# schematic.net
KiCad netlist of a schematic drawn in EAGLE
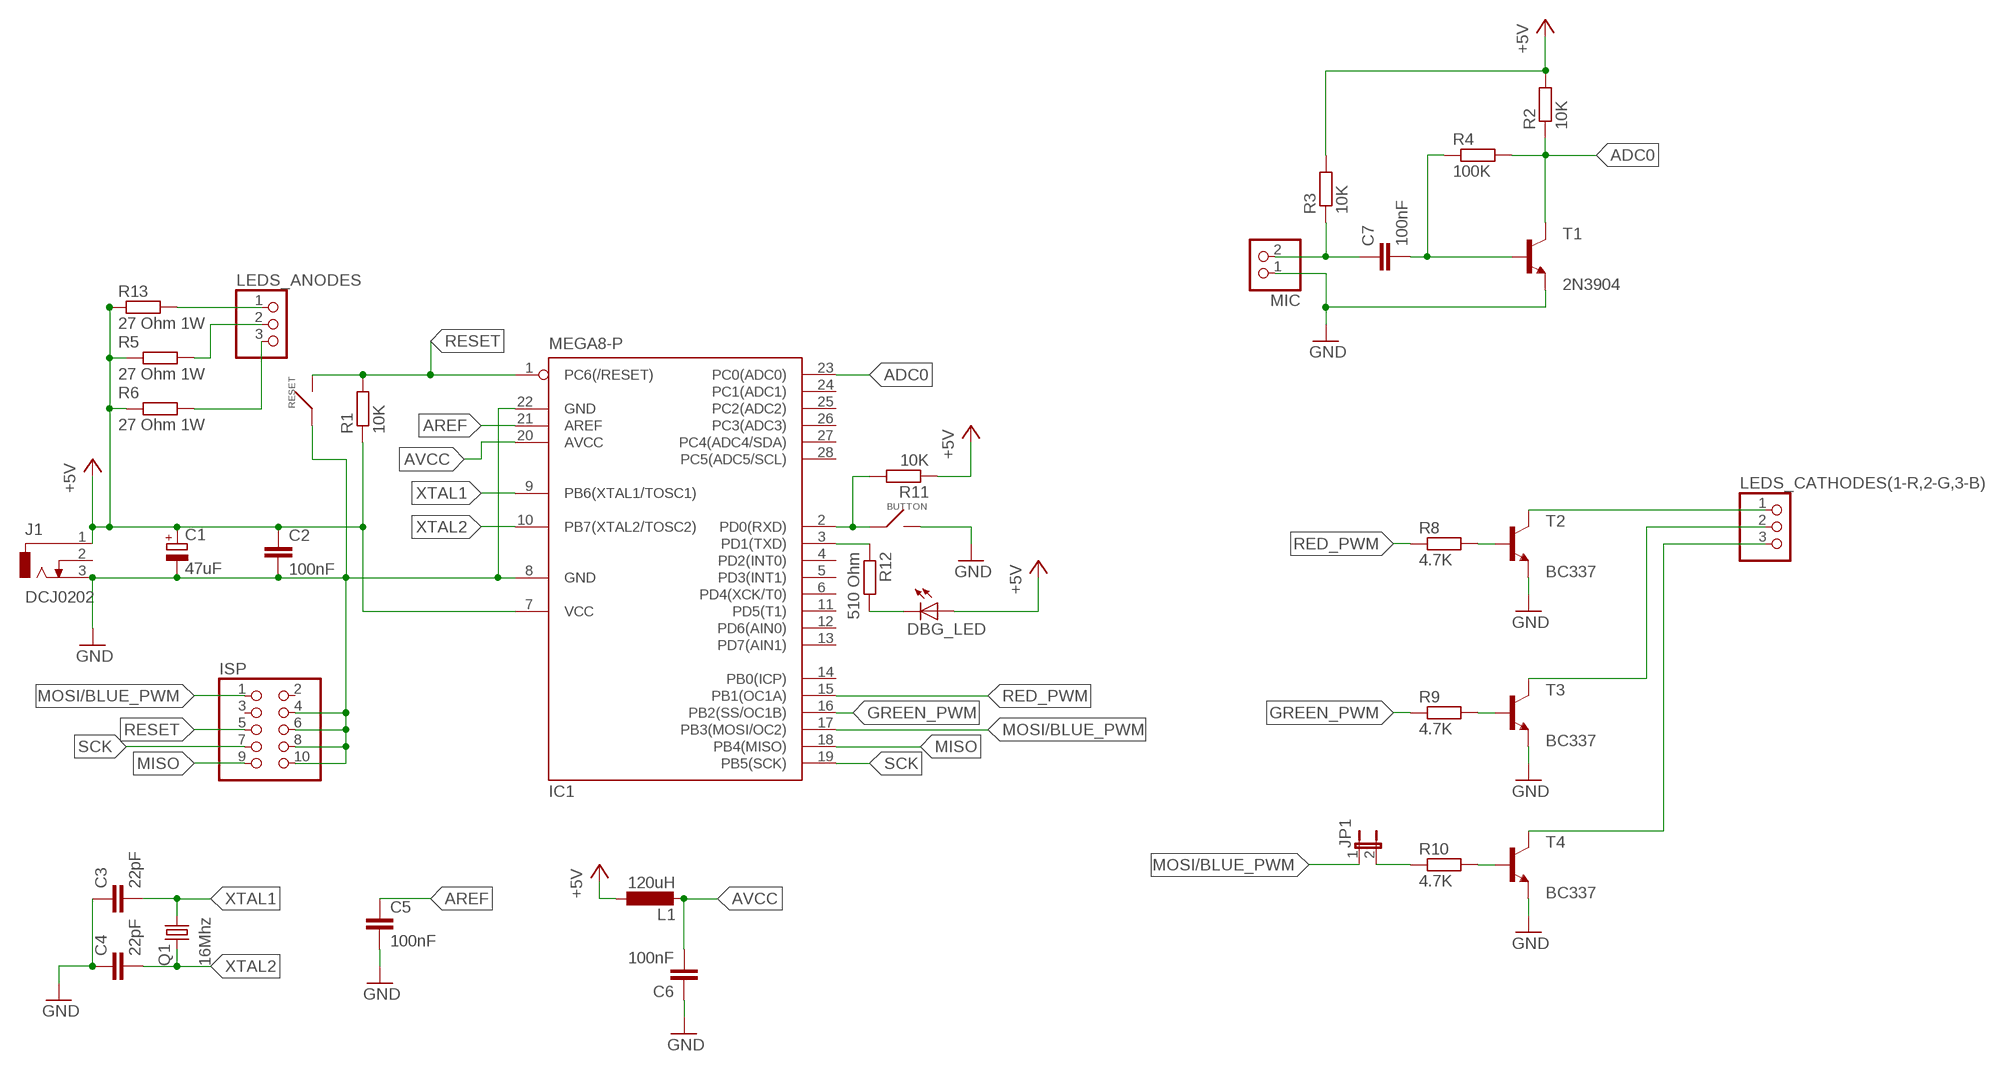
[diagram p0: schematic, sheet 1]

(export (version "E")
  (design (tool "Eeschema 10.0.6"))
  (components
    (comp (ref "BUTTON")
      (value "TS1102")
      (footprint "eagle-import:TL1105")
      (libsource (lib "eagle-import") (part "TS1102"))
    )
    (comp (ref "C1")
      (value "47uF")
      (footprint "eagle-import:E2-4")
      (libsource (lib "eagle-import") (part "CPOL-EUE2-4"))
    )
    (comp (ref "C2")
      (value "100nF")
      (footprint "eagle-import:C1206")
      (libsource (lib "eagle-import") (part "C-EUC1206"))
    )
    (comp (ref "C3")
      (value "22pF")
      (footprint "eagle-import:C050-024X044")
      (libsource (lib "eagle-import") (part "C-EU050-024X044"))
    )
    (comp (ref "C4")
      (value "22pF")
      (footprint "eagle-import:C050-024X044")
      (libsource (lib "eagle-import") (part "C-EU050-024X044"))
    )
    (comp (ref "C5")
      (value "100nF")
      (footprint "eagle-import:C1206")
      (libsource (lib "eagle-import") (part "C-EUC1206"))
    )
    (comp (ref "C6")
      (value "100nF")
      (footprint "eagle-import:C1206")
      (libsource (lib "eagle-import") (part "C-EUC1206"))
    )
    (comp (ref "C7")
      (value "100nF")
      (footprint "eagle-import:C1206")
      (libsource (lib "eagle-import") (part "C-EUC1206"))
    )
    (comp (ref "DBG_LED")
      (value "LED3MM")
      (footprint "eagle-import:LED3MM")
      (libsource (lib "eagle-import") (part "LED3MM"))
    )
    (comp (ref "IC1")
      (value "MEGA8-P")
      (footprint "eagle-import:DIL28-3")
      (libsource (lib "eagle-import") (part "MEGA8-P"))
    )
    (comp (ref "ISP")
      (value "PINHD-2X5")
      (footprint "eagle-import:2X05")
      (libsource (lib "eagle-import") (part "PINHD-2X5"))
    )
    (comp (ref "J1")
      (value "DCJ0202")
      (footprint "eagle-import:DCJ0202")
      (libsource (lib "eagle-import") (part "DCJ0202"))
    )
    (comp (ref "JP1")
      (value "JP1E")
      (footprint "eagle-import:JP1")
      (libsource (lib "eagle-import") (part "JP1E"))
    )
    (comp (ref "L1")
      (value "120uH")
      (footprint "eagle-import:2200-15.24")
      (libsource (lib "eagle-import") (part "L-EU2200-15.24"))
    )
    (comp (ref "LEDS_ANODES")
      (value "PINHD-1X3")
      (footprint "eagle-import:1X03")
      (libsource (lib "eagle-import") (part "PINHD-1X3"))
    )
    (comp (ref "LEDS_CATHODES(1-R,2-G,3-B)")
      (value "PINHD-1X3")
      (footprint "eagle-import:1X03")
      (libsource (lib "eagle-import") (part "PINHD-1X3"))
    )
    (comp (ref "MIC")
      (value "PINHD-1X2")
      (footprint "eagle-import:1X02")
      (libsource (lib "eagle-import") (part "PINHD-1X2"))
    )
    (comp (ref "Q1")
      (value "16Mhz")
      (footprint "eagle-import:HC49_S")
      (libsource (lib "eagle-import") (part "CRYSTALHC49S"))
    )
    (comp (ref "R1")
      (value "10K")
      (footprint "eagle-import:M1206")
      (libsource (lib "eagle-import") (part "R-EU_M1206"))
    )
    (comp (ref "R2")
      (value "10K")
      (footprint "eagle-import:M1206")
      (libsource (lib "eagle-import") (part "R-EU_M1206"))
    )
    (comp (ref "R3")
      (value "10K")
      (footprint "eagle-import:M1206")
      (libsource (lib "eagle-import") (part "R-EU_M1206"))
    )
    (comp (ref "R4")
      (value "100K")
      (footprint "eagle-import:M0805")
      (libsource (lib "eagle-import") (part "R-EU_M0805"))
    )
    (comp (ref "R5")
      (value "27 Ohm 1W")
      (footprint "eagle-import:0207_12")
      (libsource (lib "eagle-import") (part "R-EU_0207/12"))
    )
    (comp (ref "R6")
      (value "27 Ohm 1W")
      (footprint "eagle-import:0207_12")
      (libsource (lib "eagle-import") (part "R-EU_0207/12"))
    )
    (comp (ref "R8")
      (value "4.7K")
      (footprint "eagle-import:M0805")
      (libsource (lib "eagle-import") (part "R-EU_M0805"))
    )
    (comp (ref "R9")
      (value "4.7K")
      (footprint "eagle-import:M0805")
      (libsource (lib "eagle-import") (part "R-EU_M0805"))
    )
    (comp (ref "R10")
      (value "4.7K")
      (footprint "eagle-import:M0805")
      (libsource (lib "eagle-import") (part "R-EU_M0805"))
    )
    (comp (ref "R11")
      (value "10K")
      (footprint "eagle-import:M1206")
      (libsource (lib "eagle-import") (part "R-EU_M1206"))
    )
    (comp (ref "R12")
      (value "510 Ohm")
      (footprint "eagle-import:M1206")
      (libsource (lib "eagle-import") (part "R-EU_M1206"))
    )
    (comp (ref "R13")
      (value "27 Ohm 1W")
      (footprint "eagle-import:0207_12")
      (libsource (lib "eagle-import") (part "R-EU_0207/12"))
    )
    (comp (ref "RESET")
      (value "TS1102")
      (footprint "eagle-import:TL1105")
      (libsource (lib "eagle-import") (part "TS1102"))
    )
    (comp (ref "T1")
      (value "2N3904")
      (footprint "eagle-import:TO92")
      (libsource (lib "eagle-import") (part "2N3904"))
    )
    (comp (ref "T2")
      (value "BC337")
      (footprint "eagle-import:TO92")
      (libsource (lib "eagle-import") (part "BC337"))
    )
    (comp (ref "T3")
      (value "BC337")
      (footprint "eagle-import:TO92")
      (libsource (lib "eagle-import") (part "BC337"))
    )
    (comp (ref "T4")
      (value "BC337")
      (footprint "eagle-import:TO92")
      (libsource (lib "eagle-import") (part "BC337"))
    )
  )
  (nets
    (net (code "1") (name "+5V") (class "Default")
      (node (ref "C1") (pin "+") (pinfunction "+_+") (pintype "passive"))
      (node (ref "C2") (pin "1") (pinfunction "1_1") (pintype "passive"))
      (node (ref "DBG_LED") (pin "A") (pinfunction "A_A") (pintype "passive"))
      (node (ref "IC1") (pin "7") (pinfunction "VCC_7") (pintype "power_in"))
      (node (ref "J1") (pin "1") (pinfunction "1_1") (pintype "passive"))
      (node (ref "L1") (pin "1") (pinfunction "1_1") (pintype "passive"))
      (node (ref "R1") (pin "1") (pinfunction "1_1") (pintype "passive"))
      (node (ref "R11") (pin "1") (pinfunction "1_1") (pintype "passive"))
      (node (ref "R13") (pin "1") (pinfunction "1_1") (pintype "passive"))
      (node (ref "R2") (pin "2") (pinfunction "2_2") (pintype "passive"))
      (node (ref "R3") (pin "2") (pinfunction "2_2") (pintype "passive"))
      (node (ref "R5") (pin "1") (pinfunction "1_1") (pintype "passive"))
      (node (ref "R6") (pin "1") (pinfunction "1_1") (pintype "passive"))
    )
    (net (code "2") (name "ADC0") (class "Default")
      (node (ref "IC1") (pin "23") (pinfunction "PC0(ADC0)_23") (pintype "bidirectional"))
      (node (ref "R2") (pin "1") (pinfunction "1_1") (pintype "passive"))
      (node (ref "R4") (pin "2") (pinfunction "2_2") (pintype "passive"))
      (node (ref "T1") (pin "1") (pinfunction "C_1") (pintype "passive"))
    )
    (net (code "3") (name "AREF") (class "Default")
      (node (ref "C5") (pin "1") (pinfunction "1_1") (pintype "passive"))
      (node (ref "IC1") (pin "21") (pinfunction "AREF_21") (pintype "passive"))
    )
    (net (code "4") (name "AVCC") (class "Default")
      (node (ref "C6") (pin "2") (pinfunction "2_2") (pintype "passive"))
      (node (ref "IC1") (pin "20") (pinfunction "AVCC_20") (pintype "power_in"))
      (node (ref "L1") (pin "2") (pinfunction "2_2") (pintype "passive"))
    )
    (net (code "5") (name "GND") (class "Default")
      (node (ref "BUTTON") (pin "2") (pinfunction "P$2_2") (pintype "bidirectional"))
      (node (ref "C1") (pin "-") (pinfunction "-_-") (pintype "passive"))
      (node (ref "C2") (pin "2") (pinfunction "2_2") (pintype "passive"))
      (node (ref "C3") (pin "1") (pinfunction "1_1") (pintype "passive"))
      (node (ref "C4") (pin "1") (pinfunction "1_1") (pintype "passive"))
      (node (ref "C5") (pin "2") (pinfunction "2_2") (pintype "passive"))
      (node (ref "C6") (pin "1") (pinfunction "1_1") (pintype "passive"))
      (node (ref "IC1") (pin "22") (pinfunction "GND_22") (pintype "power_in"))
      (node (ref "IC1") (pin "8") (pinfunction "GND_8") (pintype "power_in"))
      (node (ref "ISP") (pin "10") (pinfunction "10_10") (pintype "passive"))
      (node (ref "ISP") (pin "4") (pinfunction "4_4") (pintype "passive"))
      (node (ref "ISP") (pin "6") (pinfunction "6_6") (pintype "passive"))
      (node (ref "ISP") (pin "8") (pinfunction "8_8") (pintype "passive"))
      (node (ref "J1") (pin "3") (pinfunction "3_3") (pintype "passive"))
      (node (ref "MIC") (pin "1") (pinfunction "1_1") (pintype "passive"))
      (node (ref "RESET") (pin "1") (pinfunction "P$1_1") (pintype "bidirectional"))
      (node (ref "T1") (pin "3") (pinfunction "E_3") (pintype "passive"))
      (node (ref "T2") (pin "1") (pinfunction "E_1") (pintype "passive"))
      (node (ref "T3") (pin "1") (pinfunction "E_1") (pintype "passive"))
      (node (ref "T4") (pin "1") (pinfunction "E_1") (pintype "passive"))
    )
    (net (code "6") (name "GREEN_PWM") (class "Default")
      (node (ref "IC1") (pin "16") (pinfunction "PB2(SS/OC1B)_16") (pintype "bidirectional"))
      (node (ref "R9") (pin "1") (pinfunction "1_1") (pintype "passive"))
    )
    (net (code "7") (name "MISO") (class "Default")
      (node (ref "IC1") (pin "18") (pinfunction "PB4(MISO)_18") (pintype "bidirectional"))
      (node (ref "ISP") (pin "9") (pinfunction "9_9") (pintype "passive"))
    )
    (net (code "8") (name "MOSI{slash}BLUE_PWM") (class "Default")
      (node (ref "IC1") (pin "17") (pinfunction "PB3(MOSI/OC2)_17") (pintype "bidirectional"))
      (node (ref "ISP") (pin "1") (pinfunction "1_1") (pintype "passive"))
      (node (ref "JP1") (pin "1") (pinfunction "1_1") (pintype "passive"))
    )
    (net (code "9") (name "Net-(BUTTON-P$1)") (class "Default")
      (node (ref "BUTTON") (pin "1") (pinfunction "P$1_1") (pintype "bidirectional"))
      (node (ref "IC1") (pin "2") (pinfunction "PD0(RXD)_2") (pintype "bidirectional"))
      (node (ref "R11") (pin "2") (pinfunction "2_2") (pintype "passive"))
    )
    (net (code "10") (name "Net-(C7-Pad1)") (class "Default")
      (node (ref "C7") (pin "1") (pinfunction "1_1") (pintype "passive"))
      (node (ref "MIC") (pin "2") (pinfunction "2_2") (pintype "passive"))
      (node (ref "R3") (pin "1") (pinfunction "1_1") (pintype "passive"))
    )
    (net (code "11") (name "Net-(DBG_LED-C)") (class "Default")
      (node (ref "DBG_LED") (pin "K") (pinfunction "C_K") (pintype "passive"))
      (node (ref "R12") (pin "2") (pinfunction "2_2") (pintype "passive"))
    )
    (net (code "12") (name "Net-(IC1-PD1(TXD))") (class "Default")
      (node (ref "IC1") (pin "3") (pinfunction "PD1(TXD)_3") (pintype "bidirectional"))
      (node (ref "R12") (pin "1") (pinfunction "1_1") (pintype "passive"))
    )
    (net (code "13") (name "Net-(JP1-Pad2)") (class "Default")
      (node (ref "JP1") (pin "2") (pinfunction "2_2") (pintype "passive"))
      (node (ref "R10") (pin "1") (pinfunction "1_1") (pintype "passive"))
    )
    (net (code "14") (name "Net-(LEDS_ANODES-Pad1)") (class "Default")
      (node (ref "LEDS_ANODES") (pin "1") (pinfunction "1_1") (pintype "passive"))
      (node (ref "R13") (pin "2") (pinfunction "2_2") (pintype "passive"))
    )
    (net (code "15") (name "Net-(LEDS_ANODES-Pad2)") (class "Default")
      (node (ref "LEDS_ANODES") (pin "2") (pinfunction "2_2") (pintype "passive"))
      (node (ref "R5") (pin "2") (pinfunction "2_2") (pintype "passive"))
    )
    (net (code "16") (name "Net-(LEDS_ANODES-Pad3)") (class "Default")
      (node (ref "LEDS_ANODES") (pin "3") (pinfunction "3_3") (pintype "passive"))
      (node (ref "R6") (pin "2") (pinfunction "2_2") (pintype "passive"))
    )
    (net (code "17") (name "Net-(T1-B)") (class "Default")
      (node (ref "C7") (pin "2") (pinfunction "2_2") (pintype "passive"))
      (node (ref "R4") (pin "1") (pinfunction "1_1") (pintype "passive"))
      (node (ref "T1") (pin "2") (pinfunction "B_2") (pintype "passive"))
    )
    (net (code "18") (name "Net-(T2-B)") (class "Default")
      (node (ref "R8") (pin "2") (pinfunction "2_2") (pintype "passive"))
      (node (ref "T2") (pin "2") (pinfunction "B_2") (pintype "passive"))
    )
    (net (code "19") (name "Net-(T2-C)") (class "Default")
      (node (ref "LEDS_CATHODES(1-R,2-G,3-B)") (pin "1") (pinfunction "1_1") (pintype "passive"))
      (node (ref "T2") (pin "3") (pinfunction "C_3") (pintype "passive"))
    )
    (net (code "20") (name "Net-(T3-B)") (class "Default")
      (node (ref "R9") (pin "2") (pinfunction "2_2") (pintype "passive"))
      (node (ref "T3") (pin "2") (pinfunction "B_2") (pintype "passive"))
    )
    (net (code "21") (name "Net-(T3-C)") (class "Default")
      (node (ref "LEDS_CATHODES(1-R,2-G,3-B)") (pin "2") (pinfunction "2_2") (pintype "passive"))
      (node (ref "T3") (pin "3") (pinfunction "C_3") (pintype "passive"))
    )
    (net (code "22") (name "Net-(T4-B)") (class "Default")
      (node (ref "R10") (pin "2") (pinfunction "2_2") (pintype "passive"))
      (node (ref "T4") (pin "2") (pinfunction "B_2") (pintype "passive"))
    )
    (net (code "23") (name "Net-(T4-C)") (class "Default")
      (node (ref "LEDS_CATHODES(1-R,2-G,3-B)") (pin "3") (pinfunction "3_3") (pintype "passive"))
      (node (ref "T4") (pin "3") (pinfunction "C_3") (pintype "passive"))
    )
    (net (code "24") (name "RED_PWM") (class "Default")
      (node (ref "IC1") (pin "15") (pinfunction "PB1(OC1A)_15") (pintype "bidirectional"))
      (node (ref "R8") (pin "1") (pinfunction "1_1") (pintype "passive"))
    )
    (net (code "25") (name "RESET") (class "Default")
      (node (ref "IC1") (pin "1") (pinfunction "PC6(/RESET)_1") (pintype "bidirectional"))
      (node (ref "ISP") (pin "5") (pinfunction "5_5") (pintype "passive"))
      (node (ref "R1") (pin "2") (pinfunction "2_2") (pintype "passive"))
      (node (ref "RESET") (pin "2") (pinfunction "P$2_2") (pintype "bidirectional"))
    )
    (net (code "26") (name "SCK") (class "Default")
      (node (ref "IC1") (pin "19") (pinfunction "PB5(SCK)_19") (pintype "bidirectional"))
      (node (ref "ISP") (pin "7") (pinfunction "7_7") (pintype "passive"))
    )
    (net (code "27") (name "XTAL1") (class "Default")
      (node (ref "C3") (pin "2") (pinfunction "2_2") (pintype "passive"))
      (node (ref "IC1") (pin "9") (pinfunction "PB6(XTAL1/TOSC1)_9") (pintype "bidirectional"))
      (node (ref "Q1") (pin "2") (pinfunction "2_2") (pintype "passive"))
    )
    (net (code "28") (name "XTAL2") (class "Default")
      (node (ref "C4") (pin "2") (pinfunction "2_2") (pintype "passive"))
      (node (ref "IC1") (pin "10") (pinfunction "PB7(XTAL2/TOSC2)_10") (pintype "bidirectional"))
      (node (ref "Q1") (pin "1") (pinfunction "1_1") (pintype "passive"))
    )
    (net (code "29") (name "unconnected-(IC1-PB0(ICP)-Pad14)") (class "Default")
      (node (ref "IC1") (pin "14") (pinfunction "PB0(ICP)_14") (pintype "bidirectional"))
    )
    (net (code "30") (name "unconnected-(IC1-PC1(ADC1)-Pad24)") (class "Default")
      (node (ref "IC1") (pin "24") (pinfunction "PC1(ADC1)_24") (pintype "bidirectional"))
    )
    (net (code "31") (name "unconnected-(IC1-PC2(ADC2)-Pad25)") (class "Default")
      (node (ref "IC1") (pin "25") (pinfunction "PC2(ADC2)_25") (pintype "bidirectional"))
    )
    (net (code "32") (name "unconnected-(IC1-PC3(ADC3)-Pad26)") (class "Default")
      (node (ref "IC1") (pin "26") (pinfunction "PC3(ADC3)_26") (pintype "bidirectional"))
    )
    (net (code "33") (name "unconnected-(IC1-PC4(ADC4{slash}SDA)-Pad27)") (class "Default")
      (node (ref "IC1") (pin "27") (pinfunction "PC4(ADC4/SDA)_27") (pintype "bidirectional"))
    )
    (net (code "34") (name "unconnected-(IC1-PC5(ADC5{slash}SCL)-Pad28)") (class "Default")
      (node (ref "IC1") (pin "28") (pinfunction "PC5(ADC5/SCL)_28") (pintype "bidirectional"))
    )
    (net (code "35") (name "unconnected-(IC1-PD2(INT0)-Pad4)") (class "Default")
      (node (ref "IC1") (pin "4") (pinfunction "PD2(INT0)_4") (pintype "bidirectional"))
    )
    (net (code "36") (name "unconnected-(IC1-PD3(INT1)-Pad5)") (class "Default")
      (node (ref "IC1") (pin "5") (pinfunction "PD3(INT1)_5") (pintype "bidirectional"))
    )
    (net (code "37") (name "unconnected-(IC1-PD4(XCK{slash}T0)-Pad6)") (class "Default")
      (node (ref "IC1") (pin "6") (pinfunction "PD4(XCK/T0)_6") (pintype "bidirectional"))
    )
    (net (code "38") (name "unconnected-(IC1-PD5(T1)-Pad11)") (class "Default")
      (node (ref "IC1") (pin "11") (pinfunction "PD5(T1)_11") (pintype "bidirectional"))
    )
    (net (code "39") (name "unconnected-(IC1-PD6(AIN0)-Pad12)") (class "Default")
      (node (ref "IC1") (pin "12") (pinfunction "PD6(AIN0)_12") (pintype "bidirectional"))
    )
    (net (code "40") (name "unconnected-(IC1-PD7(AIN1)-Pad13)") (class "Default")
      (node (ref "IC1") (pin "13") (pinfunction "PD7(AIN1)_13") (pintype "bidirectional"))
    )
    (net (code "41") (name "unconnected-(ISP-Pad2)") (class "Default")
      (node (ref "ISP") (pin "2") (pinfunction "2_2") (pintype "passive"))
    )
    (net (code "42") (name "unconnected-(ISP-Pad3)") (class "Default")
      (node (ref "ISP") (pin "3") (pinfunction "3_3") (pintype "passive"))
    )
    (net (code "43") (name "unconnected-(J1-Pad2)") (class "Default")
      (node (ref "J1") (pin "2") (pinfunction "2_2") (pintype "passive"))
    )
  )
)
